# potentiomer_matrix.net
KiCad netlist of a schematic drawn in EAGLE
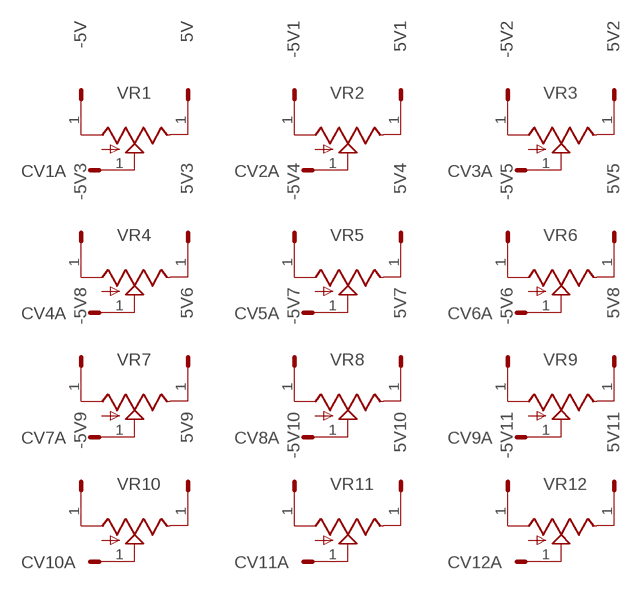
[diagram p0: schematic, sheet 1]

(export (version "E")
  (design (tool "Eeschema 10.0.6"))
  (components
    (comp (ref "-5V")
      (value "HEADER/MALE/01")
      (footprint "eagle-import:HEADER_MALE_01")
      (fields (field (name "SPICEPREFIX") "X"))
      (libsource (lib "eagle-import") (part "HEADER/MALE/01"))
    )
    (comp (ref "-5V1")
      (value "HEADER/MALE/01")
      (footprint "eagle-import:HEADER_MALE_01")
      (fields (field (name "SPICEPREFIX") "X"))
      (libsource (lib "eagle-import") (part "HEADER/MALE/01"))
    )
    (comp (ref "-5V2")
      (value "HEADER/MALE/01")
      (footprint "eagle-import:HEADER_MALE_01")
      (fields (field (name "SPICEPREFIX") "X"))
      (libsource (lib "eagle-import") (part "HEADER/MALE/01"))
    )
    (comp (ref "-5V3")
      (value "HEADER/MALE/01")
      (footprint "eagle-import:HEADER_MALE_01")
      (fields (field (name "SPICEPREFIX") "X"))
      (libsource (lib "eagle-import") (part "HEADER/MALE/01"))
    )
    (comp (ref "-5V4")
      (value "HEADER/MALE/01")
      (footprint "eagle-import:HEADER_MALE_01")
      (fields (field (name "SPICEPREFIX") "X"))
      (libsource (lib "eagle-import") (part "HEADER/MALE/01"))
    )
    (comp (ref "-5V5")
      (value "HEADER/MALE/01")
      (footprint "eagle-import:HEADER_MALE_01")
      (fields (field (name "SPICEPREFIX") "X"))
      (libsource (lib "eagle-import") (part "HEADER/MALE/01"))
    )
    (comp (ref "-5V6")
      (value "HEADER/MALE/01")
      (footprint "eagle-import:HEADER_MALE_01")
      (fields (field (name "SPICEPREFIX") "X"))
      (libsource (lib "eagle-import") (part "HEADER/MALE/01"))
    )
    (comp (ref "-5V7")
      (value "HEADER/MALE/01")
      (footprint "eagle-import:HEADER_MALE_01")
      (fields (field (name "SPICEPREFIX") "X"))
      (libsource (lib "eagle-import") (part "HEADER/MALE/01"))
    )
    (comp (ref "-5V8")
      (value "HEADER/MALE/01")
      (footprint "eagle-import:HEADER_MALE_01")
      (fields (field (name "SPICEPREFIX") "X"))
      (libsource (lib "eagle-import") (part "HEADER/MALE/01"))
    )
    (comp (ref "-5V9")
      (value "HEADER/MALE/01")
      (footprint "eagle-import:HEADER_MALE_01")
      (fields (field (name "SPICEPREFIX") "X"))
      (libsource (lib "eagle-import") (part "HEADER/MALE/01"))
    )
    (comp (ref "-5V10")
      (value "HEADER/MALE/01")
      (footprint "eagle-import:HEADER_MALE_01")
      (fields (field (name "SPICEPREFIX") "X"))
      (libsource (lib "eagle-import") (part "HEADER/MALE/01"))
    )
    (comp (ref "-5V11")
      (value "HEADER/MALE/01")
      (footprint "eagle-import:HEADER_MALE_01")
      (fields (field (name "SPICEPREFIX") "X"))
      (libsource (lib "eagle-import") (part "HEADER/MALE/01"))
    )
    (comp (ref "5V")
      (value "HEADER/MALE/01")
      (footprint "eagle-import:HEADER_MALE_01")
      (fields (field (name "SPICEPREFIX") "X"))
      (libsource (lib "eagle-import") (part "HEADER/MALE/01"))
    )
    (comp (ref "5V1")
      (value "HEADER/MALE/01")
      (footprint "eagle-import:HEADER_MALE_01")
      (fields (field (name "SPICEPREFIX") "X"))
      (libsource (lib "eagle-import") (part "HEADER/MALE/01"))
    )
    (comp (ref "5V2")
      (value "HEADER/MALE/01")
      (footprint "eagle-import:HEADER_MALE_01")
      (fields (field (name "SPICEPREFIX") "X"))
      (libsource (lib "eagle-import") (part "HEADER/MALE/01"))
    )
    (comp (ref "5V3")
      (value "HEADER/MALE/01")
      (footprint "eagle-import:HEADER_MALE_01")
      (fields (field (name "SPICEPREFIX") "X"))
      (libsource (lib "eagle-import") (part "HEADER/MALE/01"))
    )
    (comp (ref "5V4")
      (value "HEADER/MALE/01")
      (footprint "eagle-import:HEADER_MALE_01")
      (fields (field (name "SPICEPREFIX") "X"))
      (libsource (lib "eagle-import") (part "HEADER/MALE/01"))
    )
    (comp (ref "5V5")
      (value "HEADER/MALE/01")
      (footprint "eagle-import:HEADER_MALE_01")
      (fields (field (name "SPICEPREFIX") "X"))
      (libsource (lib "eagle-import") (part "HEADER/MALE/01"))
    )
    (comp (ref "5V6")
      (value "HEADER/MALE/01")
      (footprint "eagle-import:HEADER_MALE_01")
      (fields (field (name "SPICEPREFIX") "X"))
      (libsource (lib "eagle-import") (part "HEADER/MALE/01"))
    )
    (comp (ref "5V7")
      (value "HEADER/MALE/01")
      (footprint "eagle-import:HEADER_MALE_01")
      (fields (field (name "SPICEPREFIX") "X"))
      (libsource (lib "eagle-import") (part "HEADER/MALE/01"))
    )
    (comp (ref "5V8")
      (value "HEADER/MALE/01")
      (footprint "eagle-import:HEADER_MALE_01")
      (fields (field (name "SPICEPREFIX") "X"))
      (libsource (lib "eagle-import") (part "HEADER/MALE/01"))
    )
    (comp (ref "5V9")
      (value "HEADER/MALE/01")
      (footprint "eagle-import:HEADER_MALE_01")
      (fields (field (name "SPICEPREFIX") "X"))
      (libsource (lib "eagle-import") (part "HEADER/MALE/01"))
    )
    (comp (ref "5V10")
      (value "HEADER/MALE/01")
      (footprint "eagle-import:HEADER_MALE_01")
      (fields (field (name "SPICEPREFIX") "X"))
      (libsource (lib "eagle-import") (part "HEADER/MALE/01"))
    )
    (comp (ref "5V11")
      (value "HEADER/MALE/01")
      (footprint "eagle-import:HEADER_MALE_01")
      (fields (field (name "SPICEPREFIX") "X"))
      (libsource (lib "eagle-import") (part "HEADER/MALE/01"))
    )
    (comp (ref "CV1A")
      (value "HEADER/MALE/01")
      (footprint "eagle-import:HEADER_MALE_01")
      (fields (field (name "SPICEPREFIX") "X"))
      (libsource (lib "eagle-import") (part "HEADER/MALE/01"))
    )
    (comp (ref "CV2A")
      (value "HEADER/MALE/01")
      (footprint "eagle-import:HEADER_MALE_01")
      (fields (field (name "SPICEPREFIX") "X"))
      (libsource (lib "eagle-import") (part "HEADER/MALE/01"))
    )
    (comp (ref "CV3A")
      (value "HEADER/MALE/01")
      (footprint "eagle-import:HEADER_MALE_01")
      (fields (field (name "SPICEPREFIX") "X"))
      (libsource (lib "eagle-import") (part "HEADER/MALE/01"))
    )
    (comp (ref "CV4A")
      (value "HEADER/MALE/01")
      (footprint "eagle-import:HEADER_MALE_01")
      (fields (field (name "SPICEPREFIX") "X"))
      (libsource (lib "eagle-import") (part "HEADER/MALE/01"))
    )
    (comp (ref "CV5A")
      (value "HEADER/MALE/01")
      (footprint "eagle-import:HEADER_MALE_01")
      (fields (field (name "SPICEPREFIX") "X"))
      (libsource (lib "eagle-import") (part "HEADER/MALE/01"))
    )
    (comp (ref "CV6A")
      (value "HEADER/MALE/01")
      (footprint "eagle-import:HEADER_MALE_01")
      (fields (field (name "SPICEPREFIX") "X"))
      (libsource (lib "eagle-import") (part "HEADER/MALE/01"))
    )
    (comp (ref "CV7A")
      (value "HEADER/MALE/01")
      (footprint "eagle-import:HEADER_MALE_01")
      (fields (field (name "SPICEPREFIX") "X"))
      (libsource (lib "eagle-import") (part "HEADER/MALE/01"))
    )
    (comp (ref "CV8A")
      (value "HEADER/MALE/01")
      (footprint "eagle-import:HEADER_MALE_01")
      (fields (field (name "SPICEPREFIX") "X"))
      (libsource (lib "eagle-import") (part "HEADER/MALE/01"))
    )
    (comp (ref "CV9A")
      (value "HEADER/MALE/01")
      (footprint "eagle-import:HEADER_MALE_01")
      (fields (field (name "SPICEPREFIX") "X"))
      (libsource (lib "eagle-import") (part "HEADER/MALE/01"))
    )
    (comp (ref "CV10A")
      (value "HEADER/MALE/01")
      (footprint "eagle-import:HEADER_MALE_01")
      (fields (field (name "SPICEPREFIX") "X"))
      (libsource (lib "eagle-import") (part "HEADER/MALE/01"))
    )
    (comp (ref "CV11A")
      (value "HEADER/MALE/01")
      (footprint "eagle-import:HEADER_MALE_01")
      (fields (field (name "SPICEPREFIX") "X"))
      (libsource (lib "eagle-import") (part "HEADER/MALE/01"))
    )
    (comp (ref "CV12A")
      (value "HEADER/MALE/01")
      (footprint "eagle-import:HEADER_MALE_01")
      (fields (field (name "SPICEPREFIX") "X"))
      (libsource (lib "eagle-import") (part "HEADER/MALE/01"))
    )
    (comp (ref "VR1")
      (value "9MM_SNAP-IN_POT_")
      (footprint "eagle-import:9MM_SNAP-IN_POT")
      (libsource (lib "eagle-import") (part "9MM_SNAP-IN_POT_"))
    )
    (comp (ref "VR2")
      (value "9MM_SNAP-IN_POT_")
      (footprint "eagle-import:9MM_SNAP-IN_POT")
      (libsource (lib "eagle-import") (part "9MM_SNAP-IN_POT_"))
    )
    (comp (ref "VR3")
      (value "9MM_SNAP-IN_POT_")
      (footprint "eagle-import:9MM_SNAP-IN_POT")
      (libsource (lib "eagle-import") (part "9MM_SNAP-IN_POT_"))
    )
    (comp (ref "VR4")
      (value "9MM_SNAP-IN_POT_")
      (footprint "eagle-import:9MM_SNAP-IN_POT")
      (libsource (lib "eagle-import") (part "9MM_SNAP-IN_POT_"))
    )
    (comp (ref "VR5")
      (value "9MM_SNAP-IN_POT_")
      (footprint "eagle-import:9MM_SNAP-IN_POT")
      (libsource (lib "eagle-import") (part "9MM_SNAP-IN_POT_"))
    )
    (comp (ref "VR6")
      (value "9MM_SNAP-IN_POT_")
      (footprint "eagle-import:9MM_SNAP-IN_POT")
      (libsource (lib "eagle-import") (part "9MM_SNAP-IN_POT_"))
    )
    (comp (ref "VR7")
      (value "9MM_SNAP-IN_POT_")
      (footprint "eagle-import:9MM_SNAP-IN_POT")
      (libsource (lib "eagle-import") (part "9MM_SNAP-IN_POT_"))
    )
    (comp (ref "VR8")
      (value "9MM_SNAP-IN_POT_")
      (footprint "eagle-import:9MM_SNAP-IN_POT")
      (libsource (lib "eagle-import") (part "9MM_SNAP-IN_POT_"))
    )
    (comp (ref "VR9")
      (value "9MM_SNAP-IN_POT_")
      (footprint "eagle-import:9MM_SNAP-IN_POT")
      (libsource (lib "eagle-import") (part "9MM_SNAP-IN_POT_"))
    )
    (comp (ref "VR10")
      (value "9MM_SNAP-IN_POT_")
      (footprint "eagle-import:9MM_SNAP-IN_POT")
      (libsource (lib "eagle-import") (part "9MM_SNAP-IN_POT_"))
    )
    (comp (ref "VR11")
      (value "9MM_SNAP-IN_POT_")
      (footprint "eagle-import:9MM_SNAP-IN_POT")
      (libsource (lib "eagle-import") (part "9MM_SNAP-IN_POT_"))
    )
    (comp (ref "VR12")
      (value "9MM_SNAP-IN_POT_")
      (footprint "eagle-import:9MM_SNAP-IN_POT")
      (libsource (lib "eagle-import") (part "9MM_SNAP-IN_POT_"))
    )
  )
  (nets
    (net (code "1") (name "Net-(-5V-3)") (class "Default")
      (node (ref "-5V") (pin "1") (pinfunction "3_1") (pintype "passive"))
      (node (ref "VR1") (pin "1") (pinfunction "A_1") (pintype "passive"))
    )
    (net (code "2") (name "Net-(-5V1-3)") (class "Default")
      (node (ref "-5V1") (pin "1") (pinfunction "3_1") (pintype "passive"))
      (node (ref "VR2") (pin "1") (pinfunction "A_1") (pintype "passive"))
    )
    (net (code "3") (name "Net-(-5V2-3)") (class "Default")
      (node (ref "-5V2") (pin "1") (pinfunction "3_1") (pintype "passive"))
      (node (ref "VR3") (pin "1") (pinfunction "A_1") (pintype "passive"))
    )
    (net (code "4") (name "Net-(-5V3-3)") (class "Default")
      (node (ref "-5V3") (pin "1") (pinfunction "3_1") (pintype "passive"))
      (node (ref "VR4") (pin "1") (pinfunction "A_1") (pintype "passive"))
    )
    (net (code "5") (name "Net-(-5V4-3)") (class "Default")
      (node (ref "-5V4") (pin "1") (pinfunction "3_1") (pintype "passive"))
      (node (ref "VR5") (pin "1") (pinfunction "A_1") (pintype "passive"))
    )
    (net (code "6") (name "Net-(-5V5-3)") (class "Default")
      (node (ref "-5V5") (pin "1") (pinfunction "3_1") (pintype "passive"))
      (node (ref "VR6") (pin "1") (pinfunction "A_1") (pintype "passive"))
    )
    (net (code "7") (name "Net-(-5V6-3)") (class "Default")
      (node (ref "-5V6") (pin "1") (pinfunction "3_1") (pintype "passive"))
      (node (ref "VR9") (pin "1") (pinfunction "A_1") (pintype "passive"))
    )
    (net (code "8") (name "Net-(-5V7-3)") (class "Default")
      (node (ref "-5V7") (pin "1") (pinfunction "3_1") (pintype "passive"))
      (node (ref "VR8") (pin "1") (pinfunction "A_1") (pintype "passive"))
    )
    (net (code "9") (name "Net-(-5V8-3)") (class "Default")
      (node (ref "-5V8") (pin "1") (pinfunction "3_1") (pintype "passive"))
      (node (ref "VR7") (pin "1") (pinfunction "A_1") (pintype "passive"))
    )
    (net (code "10") (name "Net-(-5V9-3)") (class "Default")
      (node (ref "-5V9") (pin "1") (pinfunction "3_1") (pintype "passive"))
      (node (ref "VR10") (pin "1") (pinfunction "A_1") (pintype "passive"))
    )
    (net (code "11") (name "Net-(-5V10-3)") (class "Default")
      (node (ref "-5V10") (pin "1") (pinfunction "3_1") (pintype "passive"))
      (node (ref "VR11") (pin "1") (pinfunction "A_1") (pintype "passive"))
    )
    (net (code "12") (name "Net-(-5V11-3)") (class "Default")
      (node (ref "-5V11") (pin "1") (pinfunction "3_1") (pintype "passive"))
      (node (ref "VR12") (pin "1") (pinfunction "A_1") (pintype "passive"))
    )
    (net (code "13") (name "Net-(5V-3)") (class "Default")
      (node (ref "5V") (pin "1") (pinfunction "3_1") (pintype "passive"))
      (node (ref "VR1") (pin "3") (pinfunction "E_3") (pintype "passive"))
    )
    (net (code "14") (name "Net-(5V1-3)") (class "Default")
      (node (ref "5V1") (pin "1") (pinfunction "3_1") (pintype "passive"))
      (node (ref "VR2") (pin "3") (pinfunction "E_3") (pintype "passive"))
    )
    (net (code "15") (name "Net-(5V2-3)") (class "Default")
      (node (ref "5V2") (pin "1") (pinfunction "3_1") (pintype "passive"))
      (node (ref "VR3") (pin "3") (pinfunction "E_3") (pintype "passive"))
    )
    (net (code "16") (name "Net-(5V3-3)") (class "Default")
      (node (ref "5V3") (pin "1") (pinfunction "3_1") (pintype "passive"))
      (node (ref "VR4") (pin "3") (pinfunction "E_3") (pintype "passive"))
    )
    (net (code "17") (name "Net-(5V4-3)") (class "Default")
      (node (ref "5V4") (pin "1") (pinfunction "3_1") (pintype "passive"))
      (node (ref "VR5") (pin "3") (pinfunction "E_3") (pintype "passive"))
    )
    (net (code "18") (name "Net-(5V5-3)") (class "Default")
      (node (ref "5V5") (pin "1") (pinfunction "3_1") (pintype "passive"))
      (node (ref "VR6") (pin "3") (pinfunction "E_3") (pintype "passive"))
    )
    (net (code "19") (name "Net-(5V6-3)") (class "Default")
      (node (ref "5V6") (pin "1") (pinfunction "3_1") (pintype "passive"))
      (node (ref "VR7") (pin "3") (pinfunction "E_3") (pintype "passive"))
    )
    (net (code "20") (name "Net-(5V7-3)") (class "Default")
      (node (ref "5V7") (pin "1") (pinfunction "3_1") (pintype "passive"))
      (node (ref "VR8") (pin "3") (pinfunction "E_3") (pintype "passive"))
    )
    (net (code "21") (name "Net-(5V8-3)") (class "Default")
      (node (ref "5V8") (pin "1") (pinfunction "3_1") (pintype "passive"))
      (node (ref "VR9") (pin "3") (pinfunction "E_3") (pintype "passive"))
    )
    (net (code "22") (name "Net-(5V9-3)") (class "Default")
      (node (ref "5V9") (pin "1") (pinfunction "3_1") (pintype "passive"))
      (node (ref "VR10") (pin "3") (pinfunction "E_3") (pintype "passive"))
    )
    (net (code "23") (name "Net-(5V10-3)") (class "Default")
      (node (ref "5V10") (pin "1") (pinfunction "3_1") (pintype "passive"))
      (node (ref "VR11") (pin "3") (pinfunction "E_3") (pintype "passive"))
    )
    (net (code "24") (name "Net-(5V11-3)") (class "Default")
      (node (ref "5V11") (pin "1") (pinfunction "3_1") (pintype "passive"))
      (node (ref "VR12") (pin "3") (pinfunction "E_3") (pintype "passive"))
    )
    (net (code "25") (name "Net-(CV1A-3)") (class "Default")
      (node (ref "CV1A") (pin "1") (pinfunction "3_1") (pintype "passive"))
      (node (ref "VR1") (pin "2") (pinfunction "S_2") (pintype "passive"))
    )
    (net (code "26") (name "Net-(CV2A-3)") (class "Default")
      (node (ref "CV2A") (pin "1") (pinfunction "3_1") (pintype "passive"))
      (node (ref "VR2") (pin "2") (pinfunction "S_2") (pintype "passive"))
    )
    (net (code "27") (name "Net-(CV3A-3)") (class "Default")
      (node (ref "CV3A") (pin "1") (pinfunction "3_1") (pintype "passive"))
      (node (ref "VR3") (pin "2") (pinfunction "S_2") (pintype "passive"))
    )
    (net (code "28") (name "Net-(CV4A-3)") (class "Default")
      (node (ref "CV4A") (pin "1") (pinfunction "3_1") (pintype "passive"))
      (node (ref "VR4") (pin "2") (pinfunction "S_2") (pintype "passive"))
    )
    (net (code "29") (name "Net-(CV5A-3)") (class "Default")
      (node (ref "CV5A") (pin "1") (pinfunction "3_1") (pintype "passive"))
      (node (ref "VR5") (pin "2") (pinfunction "S_2") (pintype "passive"))
    )
    (net (code "30") (name "Net-(CV6A-3)") (class "Default")
      (node (ref "CV6A") (pin "1") (pinfunction "3_1") (pintype "passive"))
      (node (ref "VR6") (pin "2") (pinfunction "S_2") (pintype "passive"))
    )
    (net (code "31") (name "Net-(CV7A-3)") (class "Default")
      (node (ref "CV7A") (pin "1") (pinfunction "3_1") (pintype "passive"))
      (node (ref "VR7") (pin "2") (pinfunction "S_2") (pintype "passive"))
    )
    (net (code "32") (name "Net-(CV8A-3)") (class "Default")
      (node (ref "CV8A") (pin "1") (pinfunction "3_1") (pintype "passive"))
      (node (ref "VR8") (pin "2") (pinfunction "S_2") (pintype "passive"))
    )
    (net (code "33") (name "Net-(CV9A-3)") (class "Default")
      (node (ref "CV9A") (pin "1") (pinfunction "3_1") (pintype "passive"))
      (node (ref "VR9") (pin "2") (pinfunction "S_2") (pintype "passive"))
    )
    (net (code "34") (name "Net-(CV10A-3)") (class "Default")
      (node (ref "CV10A") (pin "1") (pinfunction "3_1") (pintype "passive"))
      (node (ref "VR10") (pin "2") (pinfunction "S_2") (pintype "passive"))
    )
    (net (code "35") (name "Net-(CV11A-3)") (class "Default")
      (node (ref "CV11A") (pin "1") (pinfunction "3_1") (pintype "passive"))
      (node (ref "VR11") (pin "2") (pinfunction "S_2") (pintype "passive"))
    )
    (net (code "36") (name "Net-(CV12A-3)") (class "Default")
      (node (ref "CV12A") (pin "1") (pinfunction "3_1") (pintype "passive"))
      (node (ref "VR12") (pin "2") (pinfunction "S_2") (pintype "passive"))
    )
  )
)
